# DSO_Power.net
KiCad netlist of a schematic drawn in Altium Designer
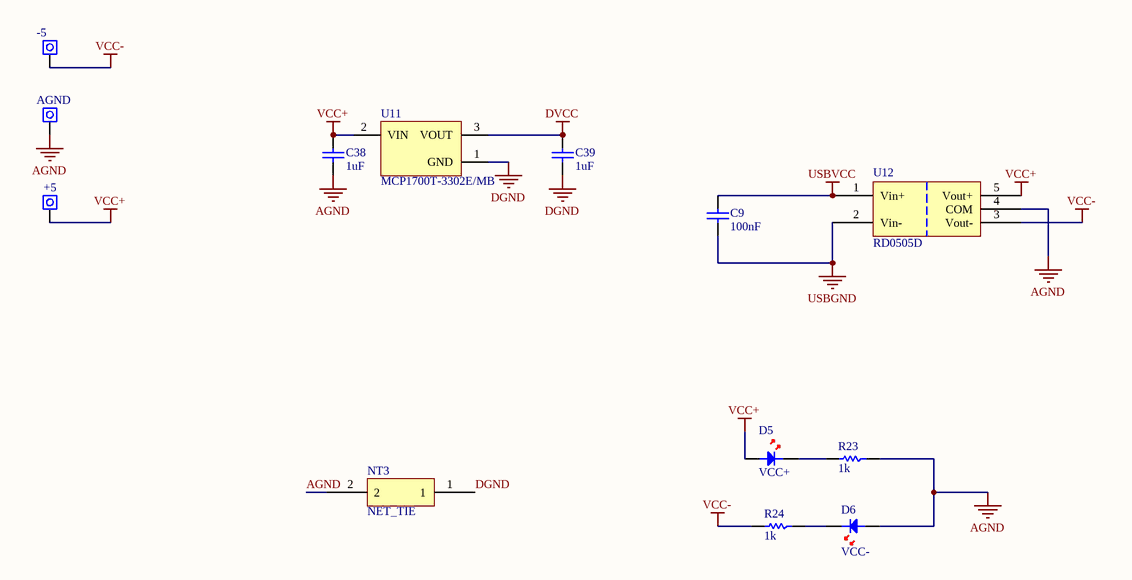
[diagram p0: DSO_Power.SchDoc]

(export (version "E")
  (design (tool "Eeschema 10.0.6"))
  (components
    (comp (ref "C9")
      (value "100nF")
      (footprint "0805C")
      (description "Capacitor")
      (fields (field (name "REVIEWED BY") "RM - 2018/08/05"))
      (libsource (lib "DSO") (part "C"))
    )
    (comp (ref "C38")
      (value "1uF")
      (footprint "0805C")
      (description "Capacitor")
      (fields (field (name "REVIEWED BY") "RM - 2018/08/05"))
      (libsource (lib "DSO") (part "C"))
    )
    (comp (ref "C39")
      (value "1uF")
      (footprint "0805C")
      (description "Capacitor")
      (fields (field (name "REVIEWED BY") "RM - 2018/08/05"))
      (libsource (lib "DSO") (part "C"))
    )
    (comp (ref "D5")
      (value "VCC+")
      (footprint "0805D-RED")
      (description "Light Emitting Diode")
      (fields (field (name "REVIEWED BY") "RM - 2018/08/05"))
      (libsource (lib "DSO") (part "LED RED"))
    )
    (comp (ref "D6")
      (value "VCC-")
      (footprint "0805D-RED")
      (description "Light Emitting Diode")
      (fields (field (name "REVIEWED BY") "RM - 2018/08/05"))
      (libsource (lib "DSO") (part "LED RED"))
    )
    (comp (ref "NT3")
      (value "NET_TIE")
      (footprint "NET_TIE")
      (description "Net Tie")
      (libsource (lib "DSO") (part "NET_TIE"))
    )
    (comp (ref "R23")
      (value "1k")
      (footprint "0805")
      (description "Resistor")
      (libsource (lib "EmbSD Lib 0v1") (part "R"))
    )
    (comp (ref "R24")
      (value "1k")
      (footprint "0805")
      (description "Resistor")
      (libsource (lib "EmbSD Lib 0v1") (part "R"))
    )
    (comp (ref "TP4")
      (value "-5")
      (footprint "PIN 1.8mm")
      (description "Pad")
      (libsource (lib "DSO") (part "WIRE"))
    )
    (comp (ref "TP5")
      (value "AGND")
      (footprint "PIN 1.8mm")
      (description "Pad")
      (libsource (lib "DSO") (part "WIRE"))
    )
    (comp (ref "TP6")
      (value "+5")
      (footprint "PIN 1.8mm")
      (description "Pad")
      (libsource (lib "DSO") (part "WIRE"))
    )
    (comp (ref "U11")
      (value "MCP1700T-3302E/MB")
      (footprint "SOT89")
      (description "Low Quiescent Current LDO, 3-Pin SOT-89, Extended Temperature, Tape and Reel")
      (fields (field (name "REVIEWED BY") "RM - 2018/08/05"))
      (libsource (lib "DSO") (part "MCP1700T"))
    )
    (comp (ref "U12")
      (value "RD0505D")
      (footprint "SIP_NMG")
      (description "(ADV) DC to DC converter 5V in +-5V out")
      (fields (field (name "REVIEWED BY") "RM - 2018/08/05"))
      (libsource (lib "DSO") (part "RD0505D"))
    )
  )
  (nets
    (net (code "1") (name "AGND") (class "Default")
      (node (ref "C38") (pin "2") (pinfunction "2_2") (pintype "passive"))
      (node (ref "D6") (pin "A") (pinfunction "A_A") (pintype "passive"))
      (node (ref "NT3") (pin "2") (pinfunction "2_2") (pintype "passive"))
      (node (ref "R23") (pin "1") (pintype "passive"))
      (node (ref "TP5") (pin "1") (pintype "passive"))
      (node (ref "U12") (pin "4") (pinfunction "COM_4") (pintype "passive"))
    )
    (net (code "2") (name "DGND") (class "Default")
      (node (ref "C39") (pin "2") (pinfunction "2_2") (pintype "passive"))
      (node (ref "NT3") (pin "1") (pinfunction "1_1") (pintype "passive"))
      (node (ref "U11") (pin "1") (pinfunction "GND_1") (pintype "power_in"))
    )
    (net (code "3") (name "DVCC") (class "Default")
      (node (ref "C39") (pin "1") (pinfunction "1_1") (pintype "passive"))
      (node (ref "U11") (pin "3") (pinfunction "VOUT_3") (pintype "power_in"))
    )
    (net (code "4") (name "Net-(D5-PadK)") (class "Default")
      (node (ref "D5") (pin "K") (pinfunction "K_K") (pintype "passive"))
      (node (ref "R23") (pin "2") (pintype "passive"))
    )
    (net (code "5") (name "Net-(D6-PadK)") (class "Default")
      (node (ref "D6") (pin "K") (pinfunction "K_K") (pintype "passive"))
      (node (ref "R24") (pin "1") (pintype "passive"))
    )
    (net (code "6") (name "USBGND") (class "Default")
      (node (ref "C9") (pin "2") (pinfunction "2_2") (pintype "passive"))
      (node (ref "U12") (pin "2") (pinfunction "Vin-_2") (pintype "passive"))
    )
    (net (code "7") (name "USBVCC") (class "Default")
      (node (ref "C9") (pin "1") (pinfunction "1_1") (pintype "passive"))
      (node (ref "U12") (pin "1") (pinfunction "Vin+_1") (pintype "passive"))
    )
    (net (code "8") (name "VCC+") (class "Default")
      (node (ref "C38") (pin "1") (pinfunction "1_1") (pintype "passive"))
      (node (ref "D5") (pin "A") (pinfunction "A_A") (pintype "passive"))
      (node (ref "TP6") (pin "1") (pintype "passive"))
      (node (ref "U11") (pin "2") (pinfunction "VIN_2") (pintype "power_in"))
      (node (ref "U12") (pin "5") (pinfunction "Vout+_5") (pintype "passive"))
    )
    (net (code "9") (name "VCC-") (class "Default")
      (node (ref "R24") (pin "2") (pintype "passive"))
      (node (ref "TP4") (pin "1") (pintype "passive"))
      (node (ref "U12") (pin "3") (pinfunction "Vout-_3") (pintype "passive"))
    )
  )
)
